# Sheet.net
KiCad netlist of a schematic drawn in Altium Designer
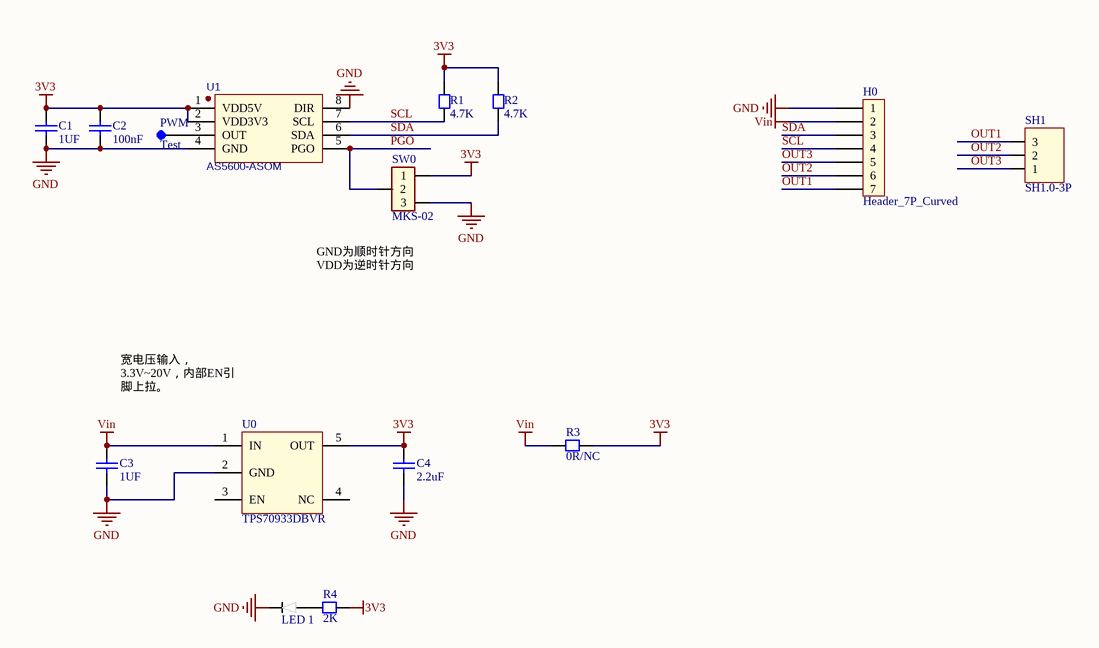
[diagram p0: Sheet.SchDoc]

(export (version "E")
  (design (tool "Eeschema 10.0.6"))
  (components
    (comp (ref "C1")
      (value "1UF")
      (footprint "CC1608-0603")
      (description "0603封装的电容")
      (fields (field (name "PUBLISHER") "Altium Limited"))
      (libsource (lib "base") (part "Cap Chip 0603"))
    )
    (comp (ref "C2")
      (value "100nF")
      (footprint "CC1608-0603")
      (description "0603封装的电容")
      (fields (field (name "PUBLISHER") "Altium Limited"))
      (libsource (lib "base") (part "Cap Chip 0603"))
    )
    (comp (ref "C3")
      (value "1UF")
      (footprint "CC1608-0603")
      (description "0603封装的电容")
      (fields (field (name "PUBLISHER") "Altium Limited"))
      (libsource (lib "base") (part "Cap Chip 0603"))
    )
    (comp (ref "C4")
      (value "2.2uF")
      (footprint "CC1608-0603")
      (description "0603封装的电容")
      (fields (field (name "PUBLISHER") "Altium Limited"))
      (libsource (lib "base") (part "Cap Chip 0603"))
    )
    (comp (ref "H0")
      (value "Header_7P_Curved")
      (footprint "Header_2_54_7PW")
      (description "弯的6P排针")
      (libsource (lib "base") (part "Header_7P_Curved"))
    )
    (comp (ref "LED 1") (value "LED 0603") (footprint "LED 0603") (libsource (lib "base") (part "LED 0603")))
    (comp (ref "PWM")
      (value "Test")
      (footprint "TEST2")
      (description "测试焊接点")
      (libsource (lib "Connectors") (part "Test"))
    )
    (comp (ref "R1")
      (value "4.7K")
      (footprint "CR1608-0603")
      (description "0603封装电阻")
      (fields (field (name "PUBLISHER") "Altium Limited"))
      (libsource (lib "base") (part "Resistor Chip 0603"))
    )
    (comp (ref "R2")
      (value "4.7K")
      (footprint "CR1608-0603")
      (description "0603封装电阻")
      (fields (field (name "PUBLISHER") "Altium Limited"))
      (libsource (lib "base") (part "Resistor Chip 0603"))
    )
    (comp (ref "R3")
      (value "0R/NC")
      (footprint "CR1608-0603")
      (description "0603封装电阻")
      (fields (field (name "PUBLISHER") "Altium Limited"))
      (libsource (lib "") (part "Resistor Chip 0603_1"))
    )
    (comp (ref "R4")
      (value "2K")
      (footprint "CR1608-0603")
      (description "0603封装电阻")
      (fields (field (name "PUBLISHER") "Altium Limited"))
      (libsource (lib "") (part "Resistor Chip 0603_2"))
    )
    (comp (ref "SH1")
      (value "SH1.0-3P")
      (footprint "SH1.0-3P")
      (description "间距为1mm的端子")
      (libsource (lib "Connectors") (part "SH1.0-3P"))
    )
    (comp (ref "SW0")
      (value "MKS-02")
      (footprint "MSK-02")
      (description "微型拨动开关")
      (libsource (lib "base") (part "sw-MSK-02"))
    )
    (comp (ref "U0")
      (value "TPS70933DBVR")
      (footprint "SOT23-5")
      (description "LDO 3.3V 150mA低压差线性稳压器芯片 超低IQ 输入2.7~30V")
      (libsource (lib "power-chip") (part "TPS70933DBVR"))
    )
    (comp (ref "U1")
      (value "AS5600-ASOM")
      (footprint "SOIC-8")
      (fields (field (name "BOM_SUPPLIER PART") "C79815"))
      (libsource (lib "PB-Chip") (part "AS5600-ASOM"))
    )
  )
  (nets
    (net (code "1") (name "/OUT1") (class "Default")
      (node (ref "H0") (pin "7") (pinfunction "7_7") (pintype "passive"))
      (node (ref "SH1") (pin "3") (pinfunction "3_3") (pintype "passive"))
    )
    (net (code "2") (name "/OUT2") (class "Default")
      (node (ref "H0") (pin "6") (pinfunction "6_6") (pintype "passive"))
      (node (ref "SH1") (pin "2") (pinfunction "2_2") (pintype "passive"))
    )
    (net (code "3") (name "/OUT3") (class "Default")
      (node (ref "H0") (pin "5") (pinfunction "5_5") (pintype "passive"))
      (node (ref "SH1") (pin "1") (pinfunction "1_1") (pintype "passive"))
    )
    (net (code "4") (name "/PGO") (class "Default")
      (node (ref "SW0") (pin "2") (pinfunction "2_2") (pintype "passive"))
      (node (ref "U1") (pin "5") (pinfunction "PGO_5") (pintype "passive"))
    )
    (net (code "5") (name "/SCL") (class "Default")
      (node (ref "H0") (pin "4") (pinfunction "4_4") (pintype "passive"))
      (node (ref "R1") (pin "1") (pinfunction "1_1") (pintype "passive"))
      (node (ref "U1") (pin "7") (pinfunction "SCL_7") (pintype "passive"))
    )
    (net (code "6") (name "/SDA") (class "Default")
      (node (ref "H0") (pin "3") (pinfunction "3_3") (pintype "passive"))
      (node (ref "R2") (pin "1") (pinfunction "1_1") (pintype "passive"))
      (node (ref "U1") (pin "6") (pinfunction "SDA_6") (pintype "passive"))
    )
    (net (code "7") (name "3V3") (class "Default")
      (node (ref "C1") (pin "2") (pinfunction "2_2") (pintype "passive"))
      (node (ref "C2") (pin "2") (pinfunction "2_2") (pintype "passive"))
      (node (ref "C4") (pin "2") (pinfunction "2_2") (pintype "passive"))
      (node (ref "R1") (pin "2") (pinfunction "2_2") (pintype "passive"))
      (node (ref "R2") (pin "2") (pinfunction "2_2") (pintype "passive"))
      (node (ref "R3") (pin "1") (pinfunction "1_1") (pintype "passive"))
      (node (ref "R4") (pin "2") (pinfunction "2_2") (pintype "passive"))
      (node (ref "SW0") (pin "1") (pinfunction "1_1") (pintype "passive"))
      (node (ref "U0") (pin "5") (pinfunction "OUT_5") (pintype "passive"))
      (node (ref "U1") (pin "1") (pinfunction "VDD5V_1") (pintype "passive"))
      (node (ref "U1") (pin "2") (pinfunction "VDD3V3_2") (pintype "passive"))
    )
    (net (code "8") (name "GND") (class "Default")
      (node (ref "C1") (pin "1") (pinfunction "1_1") (pintype "passive"))
      (node (ref "C2") (pin "1") (pinfunction "1_1") (pintype "passive"))
      (node (ref "C3") (pin "1") (pinfunction "1_1") (pintype "passive"))
      (node (ref "C4") (pin "1") (pinfunction "1_1") (pintype "passive"))
      (node (ref "H0") (pin "1") (pinfunction "1_1") (pintype "passive"))
      (node (ref "LED 1") (pin "2") (pinfunction "2_2") (pintype "passive"))
      (node (ref "SW0") (pin "3") (pinfunction "3_3") (pintype "passive"))
      (node (ref "U0") (pin "2") (pinfunction "GND_2") (pintype "passive"))
      (node (ref "U1") (pin "4") (pinfunction "GND_4") (pintype "passive"))
      (node (ref "U1") (pin "8") (pinfunction "DIR_8") (pintype "passive"))
    )
    (net (code "9") (name "Net-(LED 1-Pad1)") (class "Default")
      (node (ref "LED 1") (pin "1") (pinfunction "1_1") (pintype "passive"))
      (node (ref "R4") (pin "1") (pinfunction "1_1") (pintype "passive"))
    )
    (net (code "10") (name "Net-(U1-OUT)") (class "Default")
      (node (ref "PWM") (pin "1") (pinfunction "1_1") (pintype "passive"))
      (node (ref "U1") (pin "3") (pinfunction "OUT_3") (pintype "passive"))
    )
    (net (code "11") (name "Vin") (class "Default")
      (node (ref "C3") (pin "2") (pinfunction "2_2") (pintype "passive"))
      (node (ref "H0") (pin "2") (pinfunction "2_2") (pintype "passive"))
      (node (ref "R3") (pin "2") (pinfunction "2_2") (pintype "passive"))
      (node (ref "U0") (pin "1") (pinfunction "IN_1") (pintype "passive"))
    )
    (net (code "12") (name "unconnected-(U0-EN-Pad3)") (class "Default")
      (node (ref "U0") (pin "3") (pinfunction "EN_3") (pintype "passive"))
    )
    (net (code "13") (name "unconnected-(U0-NC-Pad4)") (class "Default")
      (node (ref "U0") (pin "4") (pinfunction "NC_4") (pintype "passive"))
    )
  )
)
